# zeta2rework_lw_v26_fixes_wompu.net
KiCad netlist of a schematic drawn in EAGLE
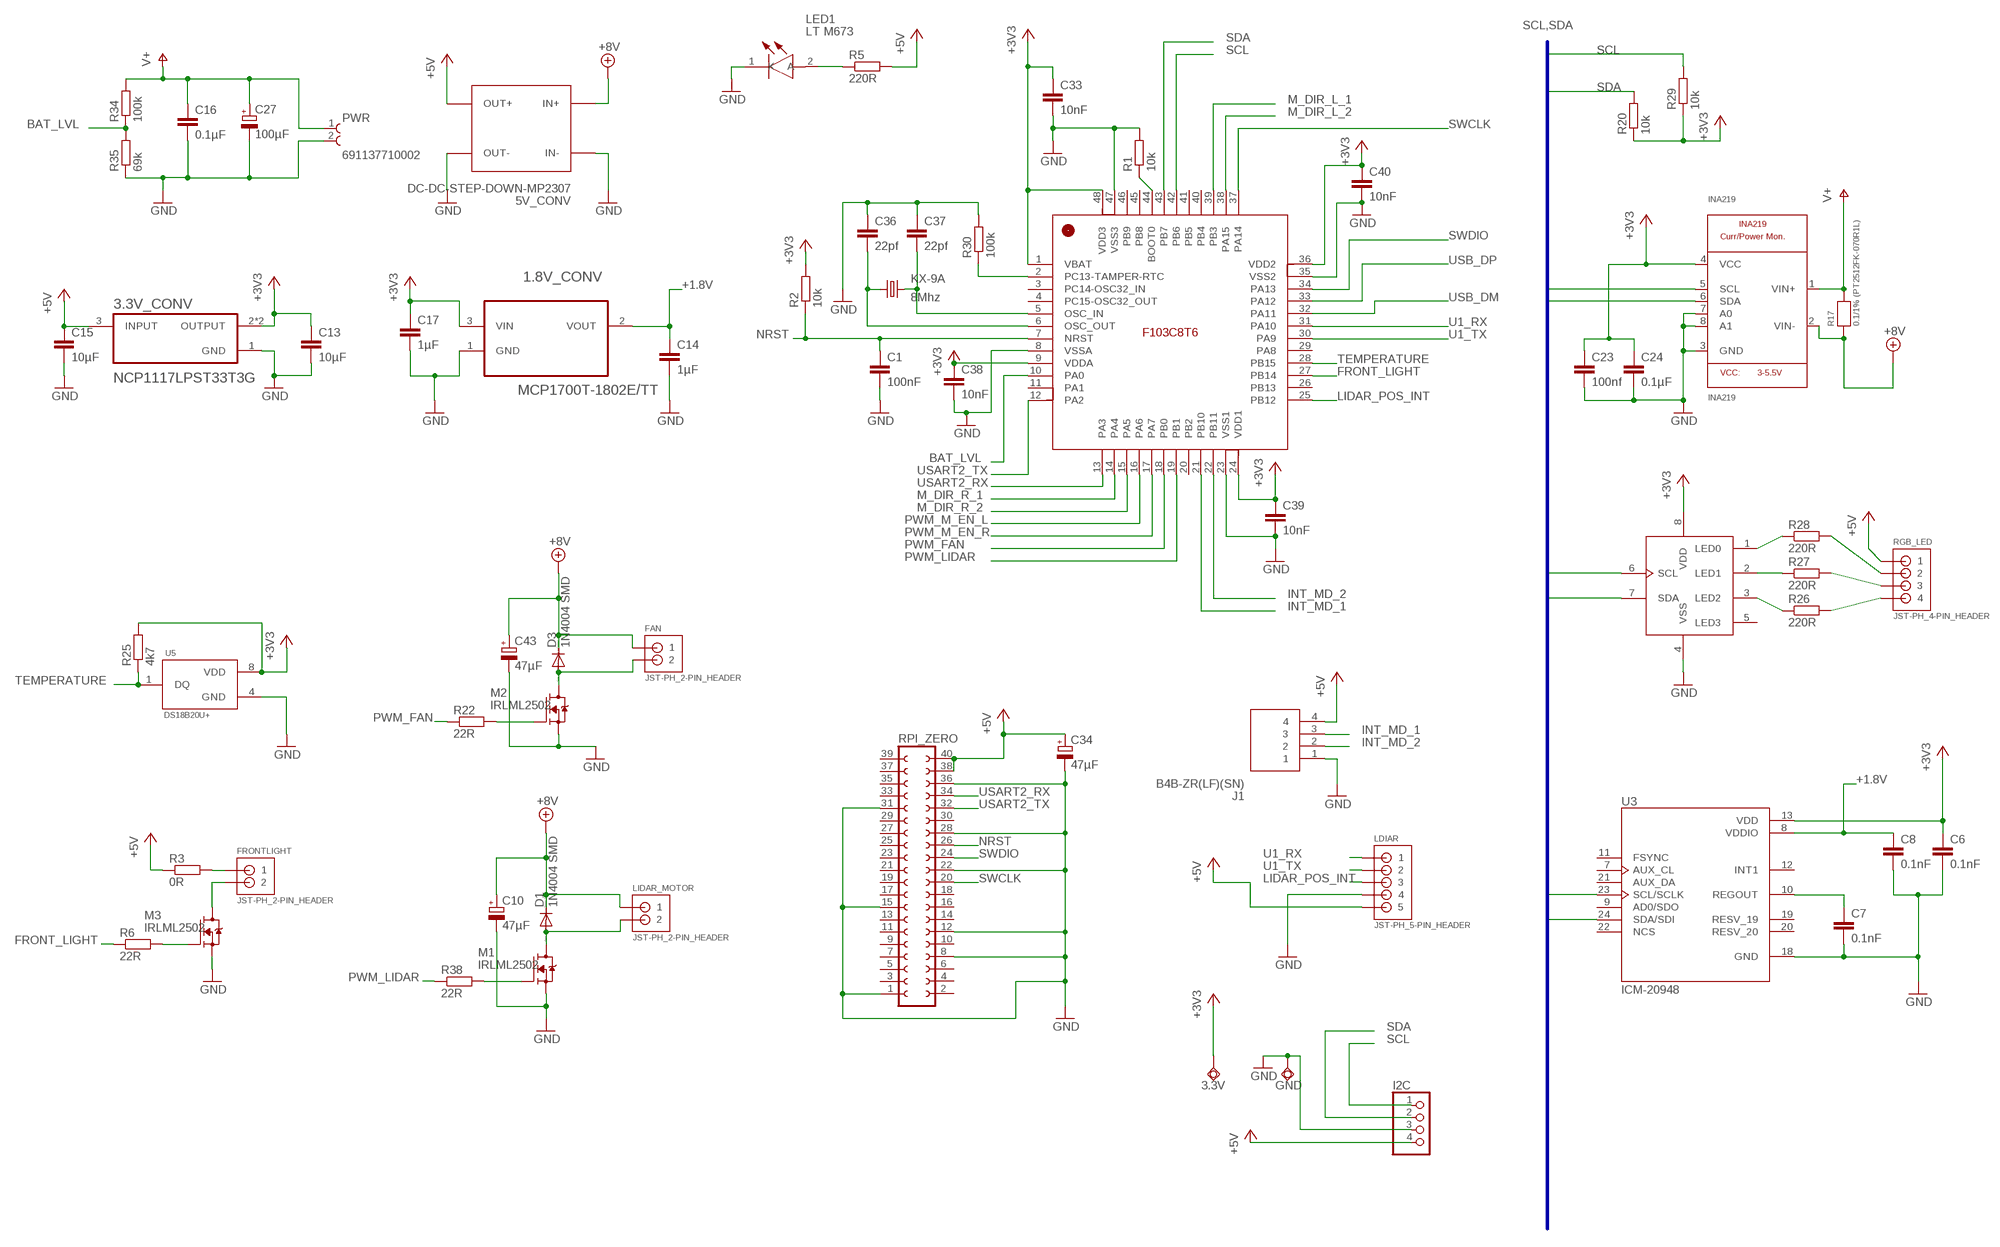
[diagram p0: schematic, sheet 1, part 1 of 2]
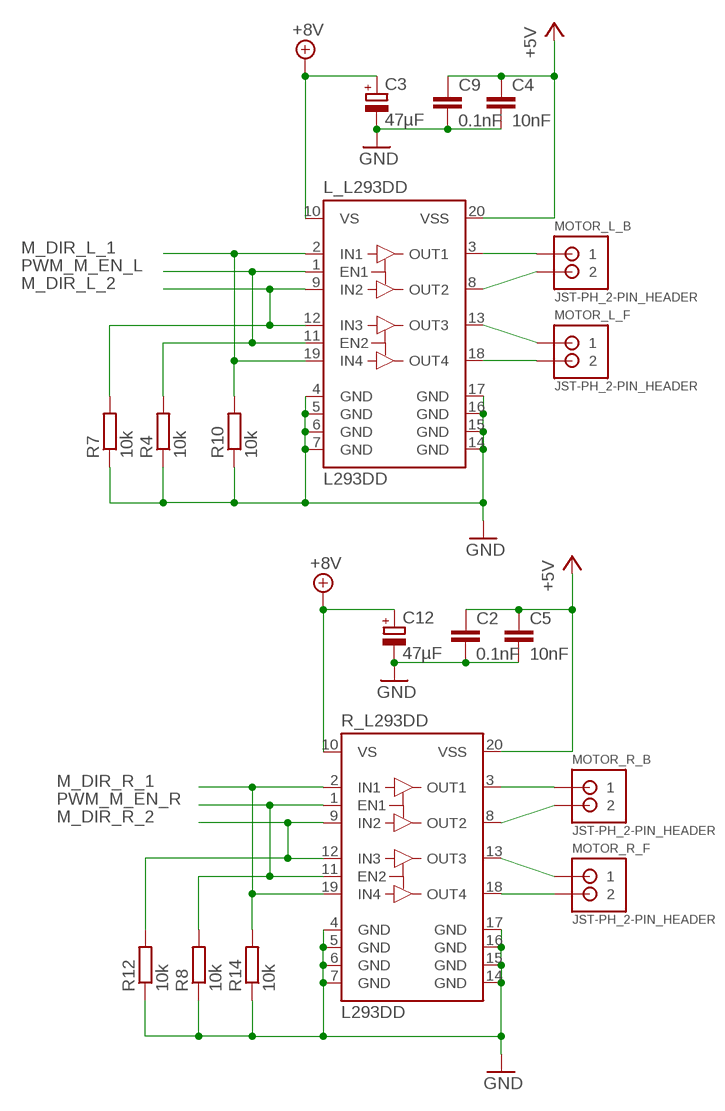
[diagram p1: schematic, sheet 1, part 2 of 2]

(export (version "E")
  (design (tool "Eeschema 10.0.6"))
  (components
    (comp (ref "1.8V_CONV")
      (value "MCP1700T-1802E/TT")
      (footprint "eagle-import:SOT95P237X112-3N")
      (fields (field (name "MF") "Microchip") (field (name "MP") "MCP1700T-2102E/TT"))
      (libsource (lib "eagle-import") (part "MCP1700T-2102E/TT"))
    )
    (comp (ref "3.3V")
      (value "TPSQTP20R")
      (footprint "eagle-import:TP20R")
      (libsource (lib "eagle-import") (part "TPSQTP20R"))
    )
    (comp (ref "3.3V_CONV")
      (value "NCP1117LPST33T3G")
      (footprint "eagle-import:SOT230P700X175-4N")
      (fields (field (name "MF") "ON Semiconductor"))
      (libsource (lib "eagle-import") (part "NCP1117LPST33T3G"))
    )
    (comp (ref "5V_CONV")
      (value "DC-DC-STEP-DOWN-MP2307")
      (footprint "eagle-import:DC-DC-STEP-DOWN-MP2307")
      (libsource (lib "eagle-import") (part "DC-DC-STEP-DOWN-MP2307"))
    )
    (comp (ref "C1")
      (value "100nF")
      (footprint "eagle-import:C1206")
      (libsource (lib "eagle-import") (part "C-EUC1206"))
    )
    (comp (ref "C2")
      (value "0.1nF")
      (footprint "eagle-import:C1206")
      (libsource (lib "eagle-import") (part "C-EUC1206"))
    )
    (comp (ref "C3")
      (value "47µF")
      (footprint "eagle-import:UD-5X5,8_NICHICON")
      (libsource (lib "eagle-import") (part "CPOL-EUUD-5X5,8"))
    )
    (comp (ref "C4")
      (value "10nF")
      (footprint "eagle-import:C1206")
      (libsource (lib "eagle-import") (part "C-EUC1206"))
    )
    (comp (ref "C5")
      (value "10nF")
      (footprint "eagle-import:C1206")
      (libsource (lib "eagle-import") (part "C-EUC1206"))
    )
    (comp (ref "C6")
      (value "0.1nF")
      (footprint "eagle-import:C1206")
      (libsource (lib "eagle-import") (part "C-EUC1206"))
    )
    (comp (ref "C7")
      (value "0.1nF")
      (footprint "eagle-import:C1206")
      (libsource (lib "eagle-import") (part "C-EUC1206"))
    )
    (comp (ref "C8")
      (value "0.1nF")
      (footprint "eagle-import:C1206")
      (libsource (lib "eagle-import") (part "C-EUC1206"))
    )
    (comp (ref "C9")
      (value "0.1nF")
      (footprint "eagle-import:C1206")
      (libsource (lib "eagle-import") (part "C-EUC1206"))
    )
    (comp (ref "C10")
      (value "47µF")
      (footprint "eagle-import:UD-5X5,8_NICHICON")
      (libsource (lib "eagle-import") (part "CPOL-EUUD-5X5,8"))
    )
    (comp (ref "C12")
      (value "47µF")
      (footprint "eagle-import:UD-5X5,8_NICHICON")
      (libsource (lib "eagle-import") (part "CPOL-EUUD-5X5,8"))
    )
    (comp (ref "C13")
      (value "10µF")
      (footprint "eagle-import:C1206")
      (libsource (lib "eagle-import") (part "C-EUC1206"))
    )
    (comp (ref "C14")
      (value "1µF")
      (footprint "eagle-import:C1206")
      (libsource (lib "eagle-import") (part "C-EUC1206"))
    )
    (comp (ref "C15")
      (value "10µF")
      (footprint "eagle-import:C1206")
      (libsource (lib "eagle-import") (part "C-EUC1206"))
    )
    (comp (ref "C16")
      (value "0.1µF")
      (footprint "eagle-import:C1206")
      (libsource (lib "eagle-import") (part "C-EUC1206"))
    )
    (comp (ref "C17")
      (value "1µF")
      (footprint "eagle-import:C1206")
      (libsource (lib "eagle-import") (part "C-EUC1206"))
    )
    (comp (ref "C23")
      (value "100nf")
      (footprint "eagle-import:C1206")
      (libsource (lib "eagle-import") (part "C-EUC1206"))
    )
    (comp (ref "C24")
      (value "0.1µF")
      (footprint "eagle-import:C1206")
      (libsource (lib "eagle-import") (part "C-EUC1206"))
    )
    (comp (ref "C27")
      (value "100µF")
      (footprint "eagle-import:UD-5X5,8_NICHICON")
      (libsource (lib "eagle-import") (part "CPOL-EUUD-5X5,8"))
    )
    (comp (ref "C33")
      (value "10nF")
      (footprint "eagle-import:C1206")
      (libsource (lib "eagle-import") (part "C-EUC1206"))
    )
    (comp (ref "C34")
      (value "47µF")
      (footprint "eagle-import:UD-5X5,8_NICHICON")
      (libsource (lib "eagle-import") (part "CPOL-EUUD-5X5,8"))
    )
    (comp (ref "C36")
      (value "22pf")
      (footprint "eagle-import:C1206")
      (libsource (lib "eagle-import") (part "C-EUC1206"))
    )
    (comp (ref "C37")
      (value "22pf")
      (footprint "eagle-import:C1206")
      (libsource (lib "eagle-import") (part "C-EUC1206"))
    )
    (comp (ref "C38")
      (value "10nF")
      (footprint "eagle-import:C1206")
      (libsource (lib "eagle-import") (part "C-EUC1206"))
    )
    (comp (ref "C39")
      (value "10nF")
      (footprint "eagle-import:C1206")
      (libsource (lib "eagle-import") (part "C-EUC1206"))
    )
    (comp (ref "C40")
      (value "10nF")
      (footprint "eagle-import:C1206")
      (libsource (lib "eagle-import") (part "C-EUC1206"))
    )
    (comp (ref "C43")
      (value "47µF")
      (footprint "eagle-import:UD-5X5,8_NICHICON")
      (libsource (lib "eagle-import") (part "CPOL-EUUD-5X5,8"))
    )
    (comp (ref "D1")
      (value "1N4004 SMD")
      (footprint "eagle-import:DO214AC")
      (libsource (lib "eagle-import") (part "DIODE-DO214AC"))
    )
    (comp (ref "D3")
      (value "1N4004 SMD")
      (footprint "eagle-import:DO214AC")
      (libsource (lib "eagle-import") (part "DIODE-DO214AC"))
    )
    (comp (ref "FAN")
      (value "JST-PH_2-PIN_HEADER")
      (footprint "eagle-import:JST_B2B-PH_HEADER")
      (libsource (lib "eagle-import") (part "JST-PH_2-PIN_HEADER"))
    )
    (comp (ref "FRONTLIGHT")
      (value "JST-PH_2-PIN_HEADER")
      (footprint "eagle-import:JST_B2B-PH_HEADER")
      (libsource (lib "eagle-import") (part "JST-PH_2-PIN_HEADER"))
    )
    (comp (ref "GND")
      (value "TPSQTP20R")
      (footprint "eagle-import:TP20R")
      (libsource (lib "eagle-import") (part "TPSQTP20R"))
    )
    (comp (ref "I2C")
      (value "PINHD-1X4")
      (footprint "eagle-import:1X04")
      (libsource (lib "eagle-import") (part "PINHD-1X4"))
    )
    (comp (ref "INA219")
      (value "INA219")
      (footprint "eagle-import:SOT23-8")
      (fields (field (name "MF") "Texas Instruments"))
      (libsource (lib "eagle-import") (part "INA219"))
    )
    (comp (ref "J1")
      (value "B4B-ZR(LF)(SN)")
      (footprint "eagle-import:SHDR4W50P0X150_1X4_750X350X450")
      (fields (field (name "FARNELL_PART_NUMBER") "9491791"))
      (libsource (lib "eagle-import") (part "B4B-ZR(LF)(SN)"))
    )
    (comp (ref "KX-9A")
      (value "8Mhz")
      (footprint "eagle-import:5.0X3.2_KX-9A")
      (libsource (lib "eagle-import") (part "KX-9A"))
    )
    (comp (ref "LDIAR")
      (value "JST-PH_5-PIN_HEADER")
      (footprint "eagle-import:JST_B5B-PH_HEADER")
      (libsource (lib "eagle-import") (part "JST-PH_5-PIN_HEADER"))
    )
    (comp (ref "LED1")
      (value "LT M673")
      (footprint "eagle-import:LTM673-N1R2-25")
      (fields
        (field (name "MANUFACTURER_PART_NUMBER") "LT M673-N1R2-25")
        (field (name "MOUSER_PART_NUMBER") "720-LTM673N1R225Z")
        (field (name "RS_PART_NUMBER") "9133231")
      )
      (libsource (lib "eagle-import") (part "LT_M673-N1R2-25"))
    )
    (comp (ref "LIDAR_MOTOR")
      (value "JST-PH_2-PIN_HEADER")
      (footprint "eagle-import:JST_B2B-PH_HEADER")
      (libsource (lib "eagle-import") (part "JST-PH_2-PIN_HEADER"))
    )
    (comp (ref "L_L293DD")
      (value "L293DD")
      (footprint "eagle-import:SO20")
      (libsource (lib "eagle-import") (part "L293DD"))
    )
    (comp (ref "M1")
      (value "IRLML2502")
      (footprint "eagle-import:SOT23")
      (fields (field (name "MF") "Infineon") (field (name "MP") "IRLML2502TRPBF"))
      (libsource (lib "eagle-import") (part "IRLML2502TRPBF"))
    )
    (comp (ref "M2")
      (value "IRLML2502")
      (footprint "eagle-import:SOT23")
      (fields (field (name "MF") "Infineon") (field (name "MP") "IRLML2502TRPBF"))
      (libsource (lib "eagle-import") (part "IRLML2502TRPBF"))
    )
    (comp (ref "M3")
      (value "IRLML2502")
      (footprint "eagle-import:SOT23")
      (fields (field (name "MF") "Infineon") (field (name "MP") "IRLML2502TRPBF"))
      (libsource (lib "eagle-import") (part "IRLML2502TRPBF"))
    )
    (comp (ref "MOTOR_L_B")
      (value "JST-PH_2-PIN_HEADER")
      (footprint "eagle-import:JST_B2B-PH_HEADER")
      (libsource (lib "eagle-import") (part "JST-PH_2-PIN_HEADER"))
    )
    (comp (ref "MOTOR_L_F")
      (value "JST-PH_2-PIN_HEADER")
      (footprint "eagle-import:JST_B2B-PH_HEADER")
      (libsource (lib "eagle-import") (part "JST-PH_2-PIN_HEADER"))
    )
    (comp (ref "MOTOR_R_B")
      (value "JST-PH_2-PIN_HEADER")
      (footprint "eagle-import:JST_B2B-PH_HEADER")
      (libsource (lib "eagle-import") (part "JST-PH_2-PIN_HEADER"))
    )
    (comp (ref "MOTOR_R_F")
      (value "JST-PH_2-PIN_HEADER")
      (footprint "eagle-import:JST_B2B-PH_HEADER")
      (libsource (lib "eagle-import") (part "JST-PH_2-PIN_HEADER"))
    )
    (comp (ref "PCA9533")
      (value "PCA9533")
      (footprint "eagle-import:SOIC8")
      (libsource (lib "eagle-import") (part "PCA9533"))
    )
    (comp (ref "PWR")
      (value "691137710002")
      (footprint "eagle-import:691137710002")
      (fields (field (name "MF") "Wurth Electronics"))
      (libsource (lib "eagle-import") (part "691137710002"))
    )
    (comp (ref "R1")
      (value "10k")
      (footprint "eagle-import:R0603")
      (libsource (lib "eagle-import") (part "R-EU_R0603"))
    )
    (comp (ref "R2")
      (value "10k")
      (footprint "eagle-import:R0603")
      (libsource (lib "eagle-import") (part "R-EU_R0603"))
    )
    (comp (ref "R3")
      (value "0R")
      (footprint "eagle-import:R0603")
      (libsource (lib "eagle-import") (part "R-EU_R0603"))
    )
    (comp (ref "R4")
      (value "10k")
      (footprint "eagle-import:R0603")
      (libsource (lib "eagle-import") (part "R-EU_R0603"))
    )
    (comp (ref "R5")
      (value "220R")
      (footprint "eagle-import:R0603")
      (libsource (lib "eagle-import") (part "R-EU_R0603"))
    )
    (comp (ref "R6")
      (value "22R")
      (footprint "eagle-import:R0603")
      (libsource (lib "eagle-import") (part "R-EU_R0603"))
    )
    (comp (ref "R7")
      (value "10k")
      (footprint "eagle-import:R0603")
      (libsource (lib "eagle-import") (part "R-EU_R0603"))
    )
    (comp (ref "R8")
      (value "10k")
      (footprint "eagle-import:R0603")
      (libsource (lib "eagle-import") (part "R-EU_R0603"))
    )
    (comp (ref "R10")
      (value "10k")
      (footprint "eagle-import:R0603")
      (libsource (lib "eagle-import") (part "R-EU_R0603"))
    )
    (comp (ref "R12")
      (value "10k")
      (footprint "eagle-import:R0603")
      (libsource (lib "eagle-import") (part "R-EU_R0603"))
    )
    (comp (ref "R14")
      (value "10k")
      (footprint "eagle-import:R0603")
      (libsource (lib "eagle-import") (part "R-EU_R0603"))
    )
    (comp (ref "R17")
      (value "0.1/1% (PT2512FK-070R1L)")
      (footprint "eagle-import:2512")
      (libsource (lib "eagle-import") (part "RESISTOR2512"))
    )
    (comp (ref "R20")
      (value "10k")
      (footprint "eagle-import:R0603")
      (libsource (lib "eagle-import") (part "R-EU_R0603"))
    )
    (comp (ref "R22")
      (value "22R")
      (footprint "eagle-import:R0603")
      (libsource (lib "eagle-import") (part "R-EU_R0603"))
    )
    (comp (ref "R25")
      (value "4k7")
      (footprint "eagle-import:R0603")
      (libsource (lib "eagle-import") (part "R-EU_R0603"))
    )
    (comp (ref "R26")
      (value "220R")
      (footprint "eagle-import:R0603")
      (libsource (lib "eagle-import") (part "R-EU_R0603"))
    )
    (comp (ref "R27")
      (value "220R")
      (footprint "eagle-import:R0603")
      (libsource (lib "eagle-import") (part "R-EU_R0603"))
    )
    (comp (ref "R28")
      (value "220R")
      (footprint "eagle-import:R0603")
      (libsource (lib "eagle-import") (part "R-EU_R0603"))
    )
    (comp (ref "R29")
      (value "10k")
      (footprint "eagle-import:R0603")
      (libsource (lib "eagle-import") (part "R-EU_R0603"))
    )
    (comp (ref "R30")
      (value "100k")
      (footprint "eagle-import:R0603")
      (libsource (lib "eagle-import") (part "R-EU_R0603"))
    )
    (comp (ref "R34")
      (value "100k")
      (footprint "eagle-import:R0603")
      (libsource (lib "eagle-import") (part "R-EU_R0603"))
    )
    (comp (ref "R35")
      (value "69k")
      (footprint "eagle-import:R0603")
      (libsource (lib "eagle-import") (part "R-EU_R0603"))
    )
    (comp (ref "R38")
      (value "22R")
      (footprint "eagle-import:R0603")
      (libsource (lib "eagle-import") (part "R-EU_R0603"))
    )
    (comp (ref "RGB_LED")
      (value "JST-PH_4-PIN_HEADER")
      (footprint "eagle-import:JST_B4B-PH_HEADER")
      (libsource (lib "eagle-import") (part "JST-PH_4-PIN_HEADER"))
    )
    (comp (ref "RPI_ZERO")
      (value "FE20-2")
      (footprint "eagle-import:FE20-2")
      (libsource (lib "eagle-import") (part "FE20-2"))
    )
    (comp (ref "R_L293DD")
      (value "L293DD")
      (footprint "eagle-import:SO20")
      (libsource (lib "eagle-import") (part "L293DD"))
    )
    (comp (ref "STM32F103CB")
      (value "STM32F103CB")
      (footprint "eagle-import:LQFP48_7X7MM_0.5MMPP")
      (fields (field (name "MF") "STMicroelectronics") (field (name "MP") "STM32F103C8T6"))
      (libsource (lib "eagle-import") (part "STM32F103C8T6"))
    )
    (comp (ref "U3")
      (value "ICM-20948")
      (footprint "eagle-import:QFN40P300X300X105-25N")
      (fields (field (name "MF") "TDK InvenSense"))
      (libsource (lib "eagle-import") (part "ICM-20948"))
    )
    (comp (ref "U5")
      (value "DS18B20U+")
      (footprint "eagle-import:SOP65P490X95-8N")
      (fields (field (name "MF") "Maxim"))
      (libsource (lib "eagle-import") (part "DS18B20U+"))
    )
  )
  (nets
    (net (code "1") (name "+3V3") (class "Default")
      (node (ref "1.8V_CONV") (pin "3") (pinfunction "VIN_3") (pintype "input"))
      (node (ref "3.3V") (pin "TP") (pinfunction "TP_TP") (pintype "input"))
      (node (ref "3.3V_CONV") (pin "2") (pinfunction "OUTPUT_2") (pintype "output"))
      (node (ref "3.3V_CONV") (pin "4") (pinfunction "OUTPUT_4") (pintype "output"))
      (node (ref "C13") (pin "1") (pinfunction "1_1") (pintype "passive"))
      (node (ref "C17") (pin "1") (pinfunction "1_1") (pintype "passive"))
      (node (ref "C23") (pin "1") (pinfunction "1_1") (pintype "passive"))
      (node (ref "C24") (pin "1") (pinfunction "1_1") (pintype "passive"))
      (node (ref "C33") (pin "1") (pinfunction "1_1") (pintype "passive"))
      (node (ref "C38") (pin "1") (pinfunction "1_1") (pintype "passive"))
      (node (ref "C39") (pin "1") (pinfunction "1_1") (pintype "passive"))
      (node (ref "C40") (pin "1") (pinfunction "1_1") (pintype "passive"))
      (node (ref "C6") (pin "1") (pinfunction "1_1") (pintype "passive"))
      (node (ref "INA219") (pin "4") (pinfunction "VCC_4") (pintype "bidirectional"))
      (node (ref "PCA9533") (pin "8") (pinfunction "VDD_8") (pintype "power_in"))
      (node (ref "R2") (pin "2") (pinfunction "2_2") (pintype "passive"))
      (node (ref "R20") (pin "1") (pinfunction "1_1") (pintype "passive"))
      (node (ref "R25") (pin "2") (pinfunction "2_2") (pintype "passive"))
      (node (ref "R29") (pin "1") (pinfunction "1_1") (pintype "passive"))
      (node (ref "STM32F103CB") (pin "1") (pinfunction "VBAT_1") (pintype "bidirectional"))
      (node (ref "STM32F103CB") (pin "24") (pinfunction "VDD1_24") (pintype "bidirectional"))
      (node (ref "STM32F103CB") (pin "36") (pinfunction "VDD2_36") (pintype "bidirectional"))
      (node (ref "STM32F103CB") (pin "48") (pinfunction "VDD3_48") (pintype "bidirectional"))
      (node (ref "STM32F103CB") (pin "9") (pinfunction "VDDA_9") (pintype "bidirectional"))
      (node (ref "U3") (pin "13") (pinfunction "VDD_13") (pintype "power_in"))
      (node (ref "U5") (pin "8") (pinfunction "VDD_8") (pintype "power_in"))
    )
    (net (code "2") (name "+5V") (class "Default")
      (node (ref "3.3V_CONV") (pin "3") (pinfunction "INPUT_3") (pintype "input"))
      (node (ref "5V_CONV") (pin "OUT+") (pinfunction "OUT+_OUT+") (pintype "bidirectional"))
      (node (ref "C15") (pin "1") (pinfunction "1_1") (pintype "passive"))
      (node (ref "C2") (pin "1") (pinfunction "1_1") (pintype "passive"))
      (node (ref "C34") (pin "+") (pinfunction "+_+") (pintype "passive"))
      (node (ref "C4") (pin "1") (pinfunction "1_1") (pintype "passive"))
      (node (ref "C5") (pin "1") (pinfunction "1_1") (pintype "passive"))
      (node (ref "C9") (pin "1") (pinfunction "1_1") (pintype "passive"))
      (node (ref "I2C") (pin "4") (pinfunction "4_4") (pintype "passive"))
      (node (ref "J1") (pin "4") (pinfunction "4_4") (pintype "bidirectional"))
      (node (ref "LDIAR") (pin "P5") (pinfunction "5_P5") (pintype "bidirectional"))
      (node (ref "L_L293DD") (pin "20") (pinfunction "VSS_20") (pintype "power_in"))
      (node (ref "R3") (pin "1") (pinfunction "1_1") (pintype "passive"))
      (node (ref "R5") (pin "2") (pinfunction "2_2") (pintype "passive"))
      (node (ref "RGB_LED") (pin "P1") (pinfunction "1_P1") (pintype "bidirectional"))
      (node (ref "RPI_ZERO") (pin "38") (pinfunction "38_38") (pintype "passive"))
      (node (ref "RPI_ZERO") (pin "40") (pinfunction "40_40") (pintype "passive"))
      (node (ref "R_L293DD") (pin "20") (pinfunction "VSS_20") (pintype "power_in"))
    )
    (net (code "3") (name "+8V") (class "Default")
      (node (ref "5V_CONV") (pin "IN+") (pinfunction "IN+_IN+") (pintype "bidirectional"))
      (node (ref "C10") (pin "+") (pinfunction "+_+") (pintype "passive"))
      (node (ref "C12") (pin "+") (pinfunction "+_+") (pintype "passive"))
      (node (ref "C3") (pin "+") (pinfunction "+_+") (pintype "passive"))
      (node (ref "C43") (pin "+") (pinfunction "+_+") (pintype "passive"))
      (node (ref "D1") (pin "C") (pinfunction "C_C") (pintype "passive"))
      (node (ref "D3") (pin "C") (pinfunction "C_C") (pintype "passive"))
      (node (ref "FAN") (pin "P1") (pinfunction "1_P1") (pintype "bidirectional"))
      (node (ref "INA219") (pin "2") (pinfunction "VIN-_2") (pintype "bidirectional"))
      (node (ref "LIDAR_MOTOR") (pin "P1") (pinfunction "1_P1") (pintype "bidirectional"))
      (node (ref "L_L293DD") (pin "10") (pinfunction "VS_10") (pintype "power_in"))
      (node (ref "R17") (pin "1") (pinfunction "1_1") (pintype "passive"))
      (node (ref "R_L293DD") (pin "10") (pinfunction "VS_10") (pintype "power_in"))
    )
    (net (code "4") (name "/+1.8V") (class "Default")
      (node (ref "1.8V_CONV") (pin "2") (pinfunction "VOUT_2") (pintype "output"))
      (node (ref "C14") (pin "1") (pinfunction "1_1") (pintype "passive"))
      (node (ref "C8") (pin "1") (pinfunction "1_1") (pintype "passive"))
      (node (ref "U3") (pin "8") (pinfunction "VDDIO_8") (pintype "power_in"))
    )
    (net (code "5") (name "/BAT_LVL") (class "Default")
      (node (ref "R34") (pin "1") (pinfunction "1_1") (pintype "passive"))
      (node (ref "R35") (pin "2") (pinfunction "2_2") (pintype "passive"))
      (node (ref "STM32F103CB") (pin "10") (pinfunction "PA0_10") (pintype "bidirectional"))
    )
    (net (code "6") (name "/FRONT_LIGHT") (class "Default")
      (node (ref "R6") (pin "1") (pinfunction "1_1") (pintype "passive"))
      (node (ref "STM32F103CB") (pin "27") (pinfunction "PB14_27") (pintype "bidirectional"))
    )
    (net (code "7") (name "/INT_MD_1") (class "Default")
      (node (ref "J1") (pin "3") (pinfunction "3_3") (pintype "bidirectional"))
      (node (ref "STM32F103CB") (pin "21") (pinfunction "PB10_21") (pintype "bidirectional"))
    )
    (net (code "8") (name "/INT_MD_2") (class "Default")
      (node (ref "J1") (pin "2") (pinfunction "2_2") (pintype "bidirectional"))
      (node (ref "STM32F103CB") (pin "22") (pinfunction "PB11_22") (pintype "bidirectional"))
    )
    (net (code "9") (name "/LIDAR_POS_INT") (class "Default")
      (node (ref "LDIAR") (pin "P3") (pinfunction "3_P3") (pintype "bidirectional"))
      (node (ref "STM32F103CB") (pin "25") (pinfunction "PB12_25") (pintype "bidirectional"))
    )
    (net (code "10") (name "/M_DIR_L_1") (class "Default")
      (node (ref "L_L293DD") (pin "19") (pinfunction "IN4_19") (pintype "input"))
      (node (ref "L_L293DD") (pin "2") (pinfunction "IN1_2") (pintype "input"))
      (node (ref "R10") (pin "2") (pinfunction "2_2") (pintype "passive"))
      (node (ref "STM32F103CB") (pin "39") (pinfunction "PB3_39") (pintype "bidirectional"))
    )
    (net (code "11") (name "/M_DIR_L_2") (class "Default")
      (node (ref "L_L293DD") (pin "12") (pinfunction "IN3_12") (pintype "input"))
      (node (ref "L_L293DD") (pin "9") (pinfunction "IN2_9") (pintype "input"))
      (node (ref "R7") (pin "2") (pinfunction "2_2") (pintype "passive"))
      (node (ref "STM32F103CB") (pin "38") (pinfunction "PA15_38") (pintype "bidirectional"))
    )
    (net (code "12") (name "/M_DIR_R_1") (class "Default")
      (node (ref "R14") (pin "2") (pinfunction "2_2") (pintype "passive"))
      (node (ref "R_L293DD") (pin "19") (pinfunction "IN4_19") (pintype "input"))
      (node (ref "R_L293DD") (pin "2") (pinfunction "IN1_2") (pintype "input"))
      (node (ref "STM32F103CB") (pin "14") (pinfunction "PA4_14") (pintype "bidirectional"))
    )
    (net (code "13") (name "/M_DIR_R_2") (class "Default")
      (node (ref "R12") (pin "2") (pinfunction "2_2") (pintype "passive"))
      (node (ref "R_L293DD") (pin "12") (pinfunction "IN3_12") (pintype "input"))
      (node (ref "R_L293DD") (pin "9") (pinfunction "IN2_9") (pintype "input"))
      (node (ref "STM32F103CB") (pin "15") (pinfunction "PA5_15") (pintype "bidirectional"))
    )
    (net (code "14") (name "/NRST") (class "Default")
      (node (ref "C1") (pin "1") (pinfunction "1_1") (pintype "passive"))
      (node (ref "R2") (pin "1") (pinfunction "1_1") (pintype "passive"))
      (node (ref "RPI_ZERO") (pin "26") (pinfunction "26_26") (pintype "passive"))
      (node (ref "STM32F103CB") (pin "7") (pinfunction "NRST_7") (pintype "bidirectional"))
    )
    (net (code "15") (name "/PWM_FAN") (class "Default")
      (node (ref "R22") (pin "1") (pinfunction "1_1") (pintype "passive"))
      (node (ref "STM32F103CB") (pin "18") (pinfunction "PB0_18") (pintype "bidirectional"))
    )
    (net (code "16") (name "/PWM_LIDAR") (class "Default")
      (node (ref "R38") (pin "1") (pinfunction "1_1") (pintype "passive"))
      (node (ref "STM32F103CB") (pin "19") (pinfunction "PB1_19") (pintype "bidirectional"))
    )
    (net (code "17") (name "/PWM_M_EN_L") (class "Default")
      (node (ref "L_L293DD") (pin "1") (pinfunction "EN1_1") (pintype "input"))
      (node (ref "L_L293DD") (pin "11") (pinfunction "EN2_11") (pintype "input"))
      (node (ref "R4") (pin "2") (pinfunction "2_2") (pintype "passive"))
      (node (ref "STM32F103CB") (pin "16") (pinfunction "PA6_16") (pintype "bidirectional"))
    )
    (net (code "18") (name "/PWM_M_EN_R") (class "Default")
      (node (ref "R8") (pin "2") (pinfunction "2_2") (pintype "passive"))
      (node (ref "R_L293DD") (pin "1") (pinfunction "EN1_1") (pintype "input"))
      (node (ref "R_L293DD") (pin "11") (pinfunction "EN2_11") (pintype "input"))
      (node (ref "STM32F103CB") (pin "17") (pinfunction "PA7_17") (pintype "bidirectional"))
    )
    (net (code "19") (name "/SCL") (class "Default")
      (node (ref "I2C") (pin "1") (pinfunction "1_1") (pintype "passive"))
      (node (ref "INA219") (pin "5") (pinfunction "SCL_5") (pintype "bidirectional"))
      (node (ref "PCA9533") (pin "6") (pinfunction "SCL_6") (pintype "input"))
      (node (ref "R29") (pin "2") (pinfunction "2_2") (pintype "passive"))
      (node (ref "STM32F103CB") (pin "42") (pinfunction "PB6_42") (pintype "bidirectional"))
      (node (ref "U3") (pin "23") (pinfunction "SCL/SCLK_23") (pintype "input"))
    )
    (net (code "20") (name "/SDA") (class "Default")
      (node (ref "I2C") (pin "2") (pinfunction "2_2") (pintype "passive"))
      (node (ref "INA219") (pin "6") (pinfunction "SDA_6") (pintype "bidirectional"))
      (node (ref "PCA9533") (pin "7") (pinfunction "SDA_7") (pintype "bidirectional"))
      (node (ref "R20") (pin "2") (pinfunction "2_2") (pintype "passive"))
      (node (ref "STM32F103CB") (pin "43") (pinfunction "PB7_43") (pintype "bidirectional"))
      (node (ref "U3") (pin "24") (pinfunction "SDA/SDI_24") (pintype "bidirectional"))
    )
    (net (code "21") (name "/SWCLK") (class "Default")
      (node (ref "RPI_ZERO") (pin "20") (pinfunction "20_20") (pintype "passive"))
      (node (ref "STM32F103CB") (pin "37") (pinfunction "PA14_37") (pintype "bidirectional"))
    )
    (net (code "22") (name "/SWDIO") (class "Default")
      (node (ref "RPI_ZERO") (pin "24") (pinfunction "24_24") (pintype "passive"))
      (node (ref "STM32F103CB") (pin "34") (pinfunction "PA13_34") (pintype "bidirectional"))
    )
    (net (code "23") (name "/TEMPERATURE") (class "Default")
      (node (ref "R25") (pin "1") (pinfunction "1_1") (pintype "passive"))
      (node (ref "STM32F103CB") (pin "28") (pinfunction "PB15_28") (pintype "bidirectional"))
      (node (ref "U5") (pin "1") (pinfunction "DQ_1") (pintype "bidirectional"))
    )
    (net (code "24") (name "/U1_RX") (class "Default")
      (node (ref "LDIAR") (pin "P1") (pinfunction "1_P1") (pintype "bidirectional"))
      (node (ref "STM32F103CB") (pin "31") (pinfunction "PA10_31") (pintype "bidirectional"))
    )
    (net (code "25") (name "/U1_TX") (class "Default")
      (node (ref "LDIAR") (pin "P2") (pinfunction "2_P2") (pintype "bidirectional"))
      (node (ref "STM32F103CB") (pin "30") (pinfunction "PA9_30") (pintype "bidirectional"))
    )
    (net (code "26") (name "/USART2_RX") (class "Default")
      (node (ref "RPI_ZERO") (pin "34") (pinfunction "34_34") (pintype "passive"))
      (node (ref "STM32F103CB") (pin "13") (pinfunction "PA3_13") (pintype "bidirectional"))
    )
    (net (code "27") (name "/USART2_TX") (class "Default")
      (node (ref "RPI_ZERO") (pin "32") (pinfunction "32_32") (pintype "passive"))
      (node (ref "STM32F103CB") (pin "12") (pinfunction "PA2_12") (pintype "bidirectional"))
    )
    (net (code "28") (name "/USB_DM") (class "Default")
      (node (ref "STM32F103CB") (pin "32") (pinfunction "PA11_32") (pintype "bidirectional"))
    )
    (net (code "29") (name "/USB_DP") (class "Default")
      (node (ref "STM32F103CB") (pin "33") (pinfunction "PA12_33") (pintype "bidirectional"))
    )
    (net (code "31") (name "GND") (class "Default")
      (node (ref "1.8V_CONV") (pin "1") (pinfunction "GND_1") (pintype "passive"))
      (node (ref "3.3V_CONV") (pin "1") (pinfunction "GND_1") (pintype "power_in"))
      (node (ref "5V_CONV") (pin "IN-") (pinfunction "IN-_IN-") (pintype "bidirectional"))
      (node (ref "5V_CONV") (pin "OUT-") (pinfunction "OUT-_OUT-") (pintype "bidirectional"))
      (node (ref "C1") (pin "2") (pinfunction "2_2") (pintype "passive"))
      (node (ref "C10") (pin "-") (pinfunction "-_-") (pintype "passive"))
      (node (ref "C12") (pin "-") (pinfunction "-_-") (pintype "passive"))
      (node (ref "C13") (pin "2") (pinfunction "2_2") (pintype "passive"))
      (node (ref "C14") (pin "2") (pinfunction "2_2") (pintype "passive"))
      (node (ref "C15") (pin "2") (pinfunction "2_2") (pintype "passive"))
      (node (ref "C16") (pin "2") (pinfunction "2_2") (pintype "passive"))
      (node (ref "C17") (pin "2") (pinfunction "2_2") (pintype "passive"))
      (node (ref "C2") (pin "2") (pinfunction "2_2") (pintype "passive"))
      (node (ref "C23") (pin "2") (pinfunction "2_2") (pintype "passive"))
      (node (ref "C24") (pin "2") (pinfunction "2_2") (pintype "passive"))
      (node (ref "C27") (pin "-") (pinfunction "-_-") (pintype "passive"))
      (node (ref "C3") (pin "-") (pinfunction "-_-") (pintype "passive"))
      (node (ref "C33") (pin "2") (pinfunction "2_2") (pintype "passive"))
      (node (ref "C34") (pin "-") (pinfunction "-_-") (pintype "passive"))
      (node (ref "C36") (pin "1") (pinfunction "1_1") (pintype "passive"))
      (node (ref "C37") (pin "1") (pinfunction "1_1") (pintype "passive"))
      (node (ref "C38") (pin "2") (pinfunction "2_2") (pintype "passive"))
      (node (ref "C39") (pin "2") (pinfunction "2_2") (pintype "passive"))
      (node (ref "C4") (pin "2") (pinfunction "2_2") (pintype "passive"))
      (node (ref "C40") (pin "2") (pinfunction "2_2") (pintype "passive"))
      (node (ref "C43") (pin "-") (pinfunction "-_-") (pintype "passive"))
      (node (ref "C5") (pin "2") (pinfunction "2_2") (pintype "passive"))
      (node (ref "C6") (pin "2") (pinfunction "2_2") (pintype "passive"))
      (node (ref "C7") (pin "2") (pinfunction "2_2") (pintype "passive"))
      (node (ref "C8") (pin "2") (pinfunction "2_2") (pintype "passive"))
      (node (ref "C9") (pin "2") (pinfunction "2_2") (pintype "passive"))
      (node (ref "GND") (pin "TP") (pinfunction "TP_TP") (pintype "input"))
      (node (ref "I2C") (pin "3") (pinfunction "3_3") (pintype "passive"))
      (node (ref "INA219") (pin "3") (pinfunction "GND_3") (pintype "bidirectional"))
      (node (ref "INA219") (pin "7") (pinfunction "A0_7") (pintype "bidirectional"))
      (node (ref "INA219") (pin "8") (pinfunction "A1_8") (pintype "bidirectional"))
      (node (ref "J1") (pin "1") (pinfunction "1_1") (pintype "bidirectional"))
      (node (ref "LDIAR") (pin "P4") (pinfunction "4_P4") (pintype "bidirectional"))
      (node (ref "LED1") (pin "1") (pinfunction "K_1") (pintype "bidirectional"))
      (node (ref "L_L293DD") (pin "14") (pinfunction "GND_14") (pintype "power_in"))
      (node (ref "L_L293DD") (pin "15") (pinfunction "GND_15") (pintype "power_in"))
      (node (ref "L_L293DD") (pin "16") (pinfunction "GND_16") (pintype "power_in"))
      (node (ref "L_L293DD") (pin "17") (pinfunction "GND_17") (pintype "power_in"))
      (node (ref "L_L293DD") (pin "4") (pinfunction "GND_4") (pintype "power_in"))
      (node (ref "L_L293DD") (pin "5") (pinfunction "GND_5") (pintype "power_in"))
      (node (ref "L_L293DD") (pin "6") (pinfunction "GND_6") (pintype "power_in"))
      (node (ref "L_L293DD") (pin "7") (pinfunction "GND_7") (pintype "power_in"))
      (node (ref "M1") (pin "2") (pinfunction "S_2") (pintype "passive"))
      (node (ref "M2") (pin "2") (pinfunction "S_2") (pintype "passive"))
      (node (ref "M3") (pin "2") (pinfunction "S_2") (pintype "passive"))
      (node (ref "PCA9533") (pin "4") (pinfunction "VSS_4") (pintype "power_in"))
      (node (ref "PWR") (pin "2") (pinfunction "2_2") (pintype "passive"))
      (node (ref "R1") (pin "2") (pinfunction "2_2") (pintype "passive"))
      (node (ref "R10") (pin "1") (pinfunction "1_1") (pintype "passive"))
      (node (ref "R12") (pin "1") (pinfunction "1_1") (pintype "passive"))
      (node (ref "R14") (pin "1") (pinfunction "1_1") (pintype "passive"))
      (node (ref "R30") (pin "2") (pinfunction "2_2") (pintype "passive"))
      (node (ref "R35") (pin "1") (pinfunction "1_1") (pintype "passive"))
      (node (ref "R4") (pin "1") (pinfunction "1_1") (pintype "passive"))
      (node (ref "R7") (pin "1") (pinfunction "1_1") (pintype "passive"))
      (node (ref "R8") (pin "1") (pinfunction "1_1") (pintype "passive"))
      (node (ref "RPI_ZERO") (pin "1") (pinfunction "1_1") (pintype "passive"))
      (node (ref "RPI_ZERO") (pin "12") (pinfunction "12_12") (pintype "passive"))
      (node (ref "RPI_ZERO") (pin "15") (pinfunction "15_15") (pintype "passive"))
      (node (ref "RPI_ZERO") (pin "22") (pinfunction "22_22") (pintype "passive"))
      (node (ref "RPI_ZERO") (pin "28") (pinfunction "28_28") (pintype "passive"))
      (node (ref "RPI_ZERO") (pin "31") (pinfunction "31_31") (pintype "passive"))
      (node (ref "RPI_ZERO") (pin "36") (pinfunction "36_36") (pintype "passive"))
      (node (ref "RPI_ZERO") (pin "8") (pinfunction "8_8") (pintype "passive"))
      (node (ref "R_L293DD") (pin "14") (pinfunction "GND_14") (pintype "power_in"))
      (node (ref "R_L293DD") (pin "15") (pinfunction "GND_15") (pintype "power_in"))
      (node (ref "R_L293DD") (pin "16") (pinfunction "GND_16") (pintype "power_in"))
      (node (ref "R_L293DD") (pin "17") (pinfunction "GND_17") (pintype "power_in"))
      (node (ref "R_L293DD") (pin "4") (pinfunction "GND_4") (pintype "power_in"))
      (node (ref "R_L293DD") (pin "5") (pinfunction "GND_5") (pintype "power_in"))
      (node (ref "R_L293DD") (pin "6") (pinfunction "GND_6") (pintype "power_in"))
      (node (ref "R_L293DD") (pin "7") (pinfunction "GND_7") (pintype "power_in"))
      (node (ref "STM32F103CB") (pin "23") (pinfunction "VSS1_23") (pintype "bidirectional"))
      (node (ref "STM32F103CB") (pin "35") (pinfunction "VSS2_35") (pintype "bidirectional"))
      (node (ref "STM32F103CB") (pin "47") (pinfunction "VSS3_47") (pintype "bidirectional"))
      (node (ref "STM32F103CB") (pin "8") (pinfunction "VSSA_8") (pintype "bidirectional"))
      (node (ref "U3") (pin "18") (pinfunction "GND_18") (pintype "power_in"))
      (node (ref "U5") (pin "4") (pinfunction "GND_4") (pintype "power_in"))
    )
    (net (code "32") (name "Net-(FAN-2)") (class "Default")
      (node (ref "D3") (pin "A") (pinfunction "A_A") (pintype "passive"))
      (node (ref "FAN") (pin "P2") (pinfunction "2_P2") (pintype "bidirectional"))
      (node (ref "M2") (pin "3") (pinfunction "D_3") (pintype "passive"))
    )
    (net (code "33") (name "Net-(FRONTLIGHT-1)") (class "Default")
      (node (ref "FRONTLIGHT") (pin "P1") (pinfunction "1_P1") (pintype "bidirectional"))
      (node (ref "R3") (pin "2") (pinfunction "2_2") (pintype "passive"))
    )
    (net (code "34") (name "Net-(FRONTLIGHT-2)") (class "Default")
      (node (ref "FRONTLIGHT") (pin "P2") (pinfunction "2_P2") (pintype "bidirectional"))
      (node (ref "M3") (pin "3") (pinfunction "D_3") (pintype "passive"))
    )
    (net (code "35") (name "Net-(KX-9A-2)") (class "Default")
      (node (ref "C37") (pin "2") (pinfunction "2_2") (pintype "passive"))
      (node (ref "KX-9A") (pin "3") (pinfunction "2_3") (pintype "passive"))
      (node (ref "STM32F103CB") (pin "5") (pinfunction "OSC_IN_5") (pintype "bidirectional"))
    )
    (net (code "36") (name "Net-(LED1-A)") (class "Default")
      (node (ref "LED1") (pin "2") (pinfunction "A_2") (pintype "bidirectional"))
      (node (ref "R5") (pin "1") (pinfunction "1_1") (pintype "passive"))
    )
    (net (code "37") (name "Net-(LIDAR_MOTOR-2)") (class "Default")
      (node (ref "D1") (pin "A") (pinfunction "A_A") (pintype "passive"))
      (node (ref "LIDAR_MOTOR") (pin "P2") (pinfunction "2_P2") (pintype "bidirectional"))
      (node (ref "M1") (pin "3") (pinfunction "D_3") (pintype "passive"))
    )
    (net (code "38") (name "Net-(L_L293DD-OUT1)") (class "Default")
      (node (ref "L_L293DD") (pin "3") (pinfunction "OUT1_3") (pintype "output"))
      (node (ref "MOTOR_L_B") (pin "P1") (pinfunction "1_P1") (pintype "bidirectional"))
    )
    (net (code "39") (name "Net-(L_L293DD-OUT2)") (class "Default")
      (node (ref "L_L293DD") (pin "8") (pinfunction "OUT2_8") (pintype "output"))
      (node (ref "MOTOR_L_B") (pin "P2") (pinfunction "2_P2") (pintype "bidirectional"))
    )
    (net (code "40") (name "Net-(L_L293DD-OUT3)") (class "Default")
      (node (ref "L_L293DD") (pin "13") (pinfunction "OUT3_13") (pintype "output"))
      (node (ref "MOTOR_L_F") (pin "P1") (pinfunction "1_P1") (pintype "bidirectional"))
    )
    (net (code "41") (name "Net-(L_L293DD-OUT4)") (class "Default")
      (node (ref "L_L293DD") (pin "18") (pinfunction "OUT4_18") (pintype "output"))
      (node (ref "MOTOR_L_F") (pin "P2") (pinfunction "2_P2") (pintype "bidirectional"))
    )
    (net (code "42") (name "Net-(M1-G)") (class "Default")
      (node (ref "M1") (pin "1") (pinfunction "G_1") (pintype "passive"))
      (node (ref "R38") (pin "2") (pinfunction "2_2") (pintype "passive"))
    )
    (net (code "43") (name "Net-(M2-G)") (class "Default")
      (node (ref "M2") (pin "1") (pinfunction "G_1") (pintype "passive"))
      (node (ref "R22") (pin "2") (pinfunction "2_2") (pintype "passive"))
    )
    (net (code "44") (name "Net-(M3-G)") (class "Default")
      (node (ref "M3") (pin "1") (pinfunction "G_1") (pintype "passive"))
      (node (ref "R6") (pin "2") (pinfunction "2_2") (pintype "passive"))
    )
    (net (code "45") (name "Net-(MOTOR_R_B-1)") (class "Default")
      (node (ref "MOTOR_R_B") (pin "P1") (pinfunction "1_P1") (pintype "bidirectional"))
      (node (ref "R_L293DD") (pin "3") (pinfunction "OUT1_3") (pintype "output"))
    )
    (net (code "46") (name "Net-(MOTOR_R_B-2)") (class "Default")
      (node (ref "MOTOR_R_B") (pin "P2") (pinfunction "2_P2") (pintype "bidirectional"))
      (node (ref "R_L293DD") (pin "8") (pinfunction "OUT2_8") (pintype "output"))
    )
    (net (code "47") (name "Net-(MOTOR_R_F-1)") (class "Default")
      (node (ref "MOTOR_R_F") (pin "P1") (pinfunction "1_P1") (pintype "bidirectional"))
      (node (ref "R_L293DD") (pin "13") (pinfunction "OUT3_13") (pintype "output"))
    )
    (net (code "48") (name "Net-(MOTOR_R_F-2)") (class "Default")
      (node (ref "MOTOR_R_F") (pin "P2") (pinfunction "2_P2") (pintype "bidirectional"))
      (node (ref "R_L293DD") (pin "18") (pinfunction "OUT4_18") (pintype "output"))
    )
    (net (code "49") (name "Net-(PCA9533-LED0)") (class "Default")
      (node (ref "PCA9533") (pin "1") (pinfunction "LED0_1") (pintype "bidirectional"))
      (node (ref "R28") (pin "1") (pinfunction "1_1") (pintype "passive"))
    )
    (net (code "50") (name "Net-(PCA9533-LED1)") (class "Default")
      (node (ref "PCA9533") (pin "2") (pinfunction "LED1_2") (pintype "bidirectional"))
      (node (ref "R27") (pin "1") (pinfunction "1_1") (pintype "passive"))
    )
    (net (code "51") (name "Net-(PCA9533-LED2)") (class "Default")
      (node (ref "PCA9533") (pin "3") (pinfunction "LED2_3") (pintype "bidirectional"))
      (node (ref "R26") (pin "1") (pinfunction "1_1") (pintype "passive"))
    )
    (net (code "52") (name "Net-(RGB_LED-2)") (class "Default")
      (node (ref "R28") (pin "2") (pinfunction "2_2") (pintype "passive"))
      (node (ref "RGB_LED") (pin "P2") (pinfunction "2_P2") (pintype "bidirectional"))
    )
    (net (code "53") (name "Net-(RGB_LED-3)") (class "Default")
      (node (ref "R27") (pin "2") (pinfunction "2_2") (pintype "passive"))
      (node (ref "RGB_LED") (pin "P3") (pinfunction "3_P3") (pintype "bidirectional"))
    )
    (net (code "54") (name "Net-(RGB_LED-4)") (class "Default")
      (node (ref "R26") (pin "2") (pinfunction "2_2") (pintype "passive"))
      (node (ref "RGB_LED") (pin "P4") (pinfunction "4_P4") (pintype "bidirectional"))
    )
    (net (code "55") (name "Net-(STM32F103CB-BOOT0)") (class "Default")
      (node (ref "R1") (pin "1") (pinfunction "1_1") (pintype "passive"))
      (node (ref "STM32F103CB") (pin "44") (pinfunction "BOOT0_44") (pintype "bidirectional"))
    )
    (net (code "56") (name "Net-(STM32F103CB-OSC_OUT)") (class "Default")
      (node (ref "C36") (pin "2") (pinfunction "2_2") (pintype "passive"))
      (node (ref "KX-9A") (pin "1") (pinfunction "1_1") (pintype "passive"))
      (node (ref "STM32F103CB") (pin "6") (pinfunction "OSC_OUT_6") (pintype "bidirectional"))
    )
    (net (code "57") (name "Net-(STM32F103CB-PC13-TAMPER-RTC)") (class "Default")
      (node (ref "R30") (pin "1") (pinfunction "1_1") (pintype "passive"))
      (node (ref "STM32F103CB") (pin "2") (pinfunction "PC13-TAMPER-RTC_2") (pintype "bidirectional"))
    )
    (net (code "58") (name "Net-(U3-REGOUT)") (class "Default")
      (node (ref "C7") (pin "1") (pinfunction "1_1") (pintype "passive"))
      (node (ref "U3") (pin "10") (pinfunction "REGOUT_10") (pintype "output"))
    )
    (net (code "59") (name "V+") (class "Default")
      (node (ref "C16") (pin "1") (pinfunction "1_1") (pintype "passive"))
      (node (ref "C27") (pin "+") (pinfunction "+_+") (pintype "passive"))
      (node (ref "INA219") (pin "1") (pinfunction "VIN+_1") (pintype "bidirectional"))
      (node (ref "PWR") (pin "1") (pinfunction "1_1") (pintype "passive"))
      (node (ref "R17") (pin "2") (pinfunction "2_2") (pintype "passive"))
      (node (ref "R34") (pin "2") (pinfunction "2_2") (pintype "passive"))
    )
    (net (code "60") (name "unconnected-(PCA9533-LED3-Pad5)") (class "Default")
      (node (ref "PCA9533") (pin "5") (pinfunction "LED3_5") (pintype "bidirectional"))
    )
    (net (code "61") (name "unconnected-(RPI_ZERO-Pad2)") (class "Default")
      (node (ref "RPI_ZERO") (pin "2") (pinfunction "2_2") (pintype "passive"))
    )
    (net (code "62") (name "unconnected-(RPI_ZERO-Pad3)") (class "Default")
      (node (ref "RPI_ZERO") (pin "3") (pinfunction "3_3") (pintype "passive"))
    )
    (net (code "63") (name "unconnected-(RPI_ZERO-Pad4)") (class "Default")
      (node (ref "RPI_ZERO") (pin "4") (pinfunction "4_4") (pintype "passive"))
    )
    (net (code "64") (name "unconnected-(RPI_ZERO-Pad5)") (class "Default")
      (node (ref "RPI_ZERO") (pin "5") (pinfunction "5_5") (pintype "passive"))
    )
    (net (code "65") (name "unconnected-(RPI_ZERO-Pad6)") (class "Default")
      (node (ref "RPI_ZERO") (pin "6") (pinfunction "6_6") (pintype "passive"))
    )
    (net (code "66") (name "unconnected-(RPI_ZERO-Pad7)") (class "Default")
      (node (ref "RPI_ZERO") (pin "7") (pinfunction "7_7") (pintype "passive"))
    )
    (net (code "67") (name "unconnected-(RPI_ZERO-Pad9)") (class "Default")
      (node (ref "RPI_ZERO") (pin "9") (pinfunction "9_9") (pintype "passive"))
    )
    (net (code "68") (name "unconnected-(RPI_ZERO-Pad10)") (class "Default")
      (node (ref "RPI_ZERO") (pin "10") (pinfunction "10_10") (pintype "passive"))
    )
    (net (code "69") (name "unconnected-(RPI_ZERO-Pad11)") (class "Default")
      (node (ref "RPI_ZERO") (pin "11") (pinfunction "11_11") (pintype "passive"))
    )
    (net (code "70") (name "unconnected-(RPI_ZERO-Pad13)") (class "Default")
      (node (ref "RPI_ZERO") (pin "13") (pinfunction "13_13") (pintype "passive"))
    )
    (net (code "71") (name "unconnected-(RPI_ZERO-Pad14)") (class "Default")
      (node (ref "RPI_ZERO") (pin "14") (pinfunction "14_14") (pintype "passive"))
    )
    (net (code "72") (name "unconnected-(RPI_ZERO-Pad16)") (class "Default")
      (node (ref "RPI_ZERO") (pin "16") (pinfunction "16_16") (pintype "passive"))
    )
    (net (code "73") (name "unconnected-(RPI_ZERO-Pad17)") (class "Default")
      (node (ref "RPI_ZERO") (pin "17") (pinfunction "17_17") (pintype "passive"))
    )
    (net (code "74") (name "unconnected-(RPI_ZERO-Pad18)") (class "Default")
      (node (ref "RPI_ZERO") (pin "18") (pinfunction "18_18") (pintype "passive"))
    )
    (net (code "75") (name "unconnected-(RPI_ZERO-Pad19)") (class "Default")
      (node (ref "RPI_ZERO") (pin "19") (pinfunction "19_19") (pintype "passive"))
    )
    (net (code "76") (name "unconnected-(RPI_ZERO-Pad21)") (class "Default")
      (node (ref "RPI_ZERO") (pin "21") (pinfunction "21_21") (pintype "passive"))
    )
    (net (code "77") (name "unconnected-(RPI_ZERO-Pad23)") (class "Default")
      (node (ref "RPI_ZERO") (pin "23") (pinfunction "23_23") (pintype "passive"))
    )
    (net (code "78") (name "unconnected-(RPI_ZERO-Pad25)") (class "Default")
      (node (ref "RPI_ZERO") (pin "25") (pinfunction "25_25") (pintype "passive"))
    )
    (net (code "79") (name "unconnected-(RPI_ZERO-Pad27)") (class "Default")
      (node (ref "RPI_ZERO") (pin "27") (pinfunction "27_27") (pintype "passive"))
    )
    (net (code "80") (name "unconnected-(RPI_ZERO-Pad29)") (class "Default")
      (node (ref "RPI_ZERO") (pin "29") (pinfunction "29_29") (pintype "passive"))
    )
    (net (code "81") (name "unconnected-(RPI_ZERO-Pad30)") (class "Default")
      (node (ref "RPI_ZERO") (pin "30") (pinfunction "30_30") (pintype "passive"))
    )
    (net (code "82") (name "unconnected-(RPI_ZERO-Pad33)") (class "Default")
      (node (ref "RPI_ZERO") (pin "33") (pinfunction "33_33") (pintype "passive"))
    )
    (net (code "83") (name "unconnected-(RPI_ZERO-Pad35)") (class "Default")
      (node (ref "RPI_ZERO") (pin "35") (pinfunction "35_35") (pintype "passive"))
    )
    (net (code "84") (name "unconnected-(RPI_ZERO-Pad37)") (class "Default")
      (node (ref "RPI_ZERO") (pin "37") (pinfunction "37_37") (pintype "passive"))
    )
    (net (code "85") (name "unconnected-(RPI_ZERO-Pad39)") (class "Default")
      (node (ref "RPI_ZERO") (pin "39") (pinfunction "39_39") (pintype "passive"))
    )
    (net (code "86") (name "unconnected-(STM32F103CB-PA1-Pad11)") (class "Default")
      (node (ref "STM32F103CB") (pin "11") (pinfunction "PA1_11") (pintype "bidirectional"))
    )
    (net (code "87") (name "unconnected-(STM32F103CB-PA8-Pad29)") (class "Default")
      (node (ref "STM32F103CB") (pin "29") (pinfunction "PA8_29") (pintype "bidirectional"))
    )
    (net (code "88") (name "unconnected-(STM32F103CB-PB2-Pad20)") (class "Default")
      (node (ref "STM32F103CB") (pin "20") (pinfunction "PB2_20") (pintype "bidirectional"))
    )
    (net (code "89") (name "unconnected-(STM32F103CB-PB4-Pad40)") (class "Default")
      (node (ref "STM32F103CB") (pin "40") (pinfunction "PB4_40") (pintype "bidirectional"))
    )
    (net (code "90") (name "unconnected-(STM32F103CB-PB5-Pad41)") (class "Default")
      (node (ref "STM32F103CB") (pin "41") (pinfunction "PB5_41") (pintype "bidirectional"))
    )
    (net (code "91") (name "unconnected-(STM32F103CB-PB8-Pad45)") (class "Default")
      (node (ref "STM32F103CB") (pin "45") (pinfunction "PB8_45") (pintype "bidirectional"))
    )
    (net (code "92") (name "unconnected-(STM32F103CB-PB9-Pad46)") (class "Default")
      (node (ref "STM32F103CB") (pin "46") (pinfunction "PB9_46") (pintype "bidirectional"))
    )
    (net (code "93") (name "unconnected-(STM32F103CB-PB13-Pad26)") (class "Default")
      (node (ref "STM32F103CB") (pin "26") (pinfunction "PB13_26") (pintype "bidirectional"))
    )
    (net (code "94") (name "unconnected-(STM32F103CB-PC14-OSC32_IN-Pad3)") (class "Default")
      (node (ref "STM32F103CB") (pin "3") (pinfunction "PC14-OSC32_IN_3") (pintype "bidirectional"))
    )
    (net (code "95") (name "unconnected-(STM32F103CB-PC15-OSC32_OUT-Pad4)") (class "Default")
      (node (ref "STM32F103CB") (pin "4") (pinfunction "PC15-OSC32_OUT_4") (pintype "bidirectional"))
    )
    (net (code "96") (name "unconnected-(U3-AD0{slash}SDO-Pad9)") (class "Default")
      (node (ref "U3") (pin "9") (pinfunction "AD0/SDO_9") (pintype "output"))
    )
    (net (code "97") (name "unconnected-(U3-AUX_CL-Pad7)") (class "Default")
      (node (ref "U3") (pin "7") (pinfunction "AUX_CL_7") (pintype "input"))
    )
    (net (code "98") (name "unconnected-(U3-AUX_DA-Pad21)") (class "Default")
      (node (ref "U3") (pin "21") (pinfunction "AUX_DA_21") (pintype "input"))
    )
    (net (code "99") (name "unconnected-(U3-FSYNC-Pad11)") (class "Default")
      (node (ref "U3") (pin "11") (pinfunction "FSYNC_11") (pintype "input"))
    )
    (net (code "100") (name "unconnected-(U3-INT1-Pad12)") (class "Default")
      (node (ref "U3") (pin "12") (pinfunction "INT1_12") (pintype "output"))
    )
    (net (code "101") (name "unconnected-(U3-NCS-Pad22)") (class "Default")
      (node (ref "U3") (pin "22") (pinfunction "NCS_22") (pintype "input"))
    )
    (net (code "102") (name "unconnected-(U3-RESV_19-Pad19)") (class "Default")
      (node (ref "U3") (pin "19") (pinfunction "RESV_19_19") (pintype "passive"))
    )
    (net (code "103") (name "unconnected-(U3-RESV_20-Pad20)") (class "Default")
      (node (ref "U3") (pin "20") (pinfunction "RESV_20_20") (pintype "passive"))
    )
  )
)
